# schematic.net
KiCad netlist of a schematic drawn in EasyEDA
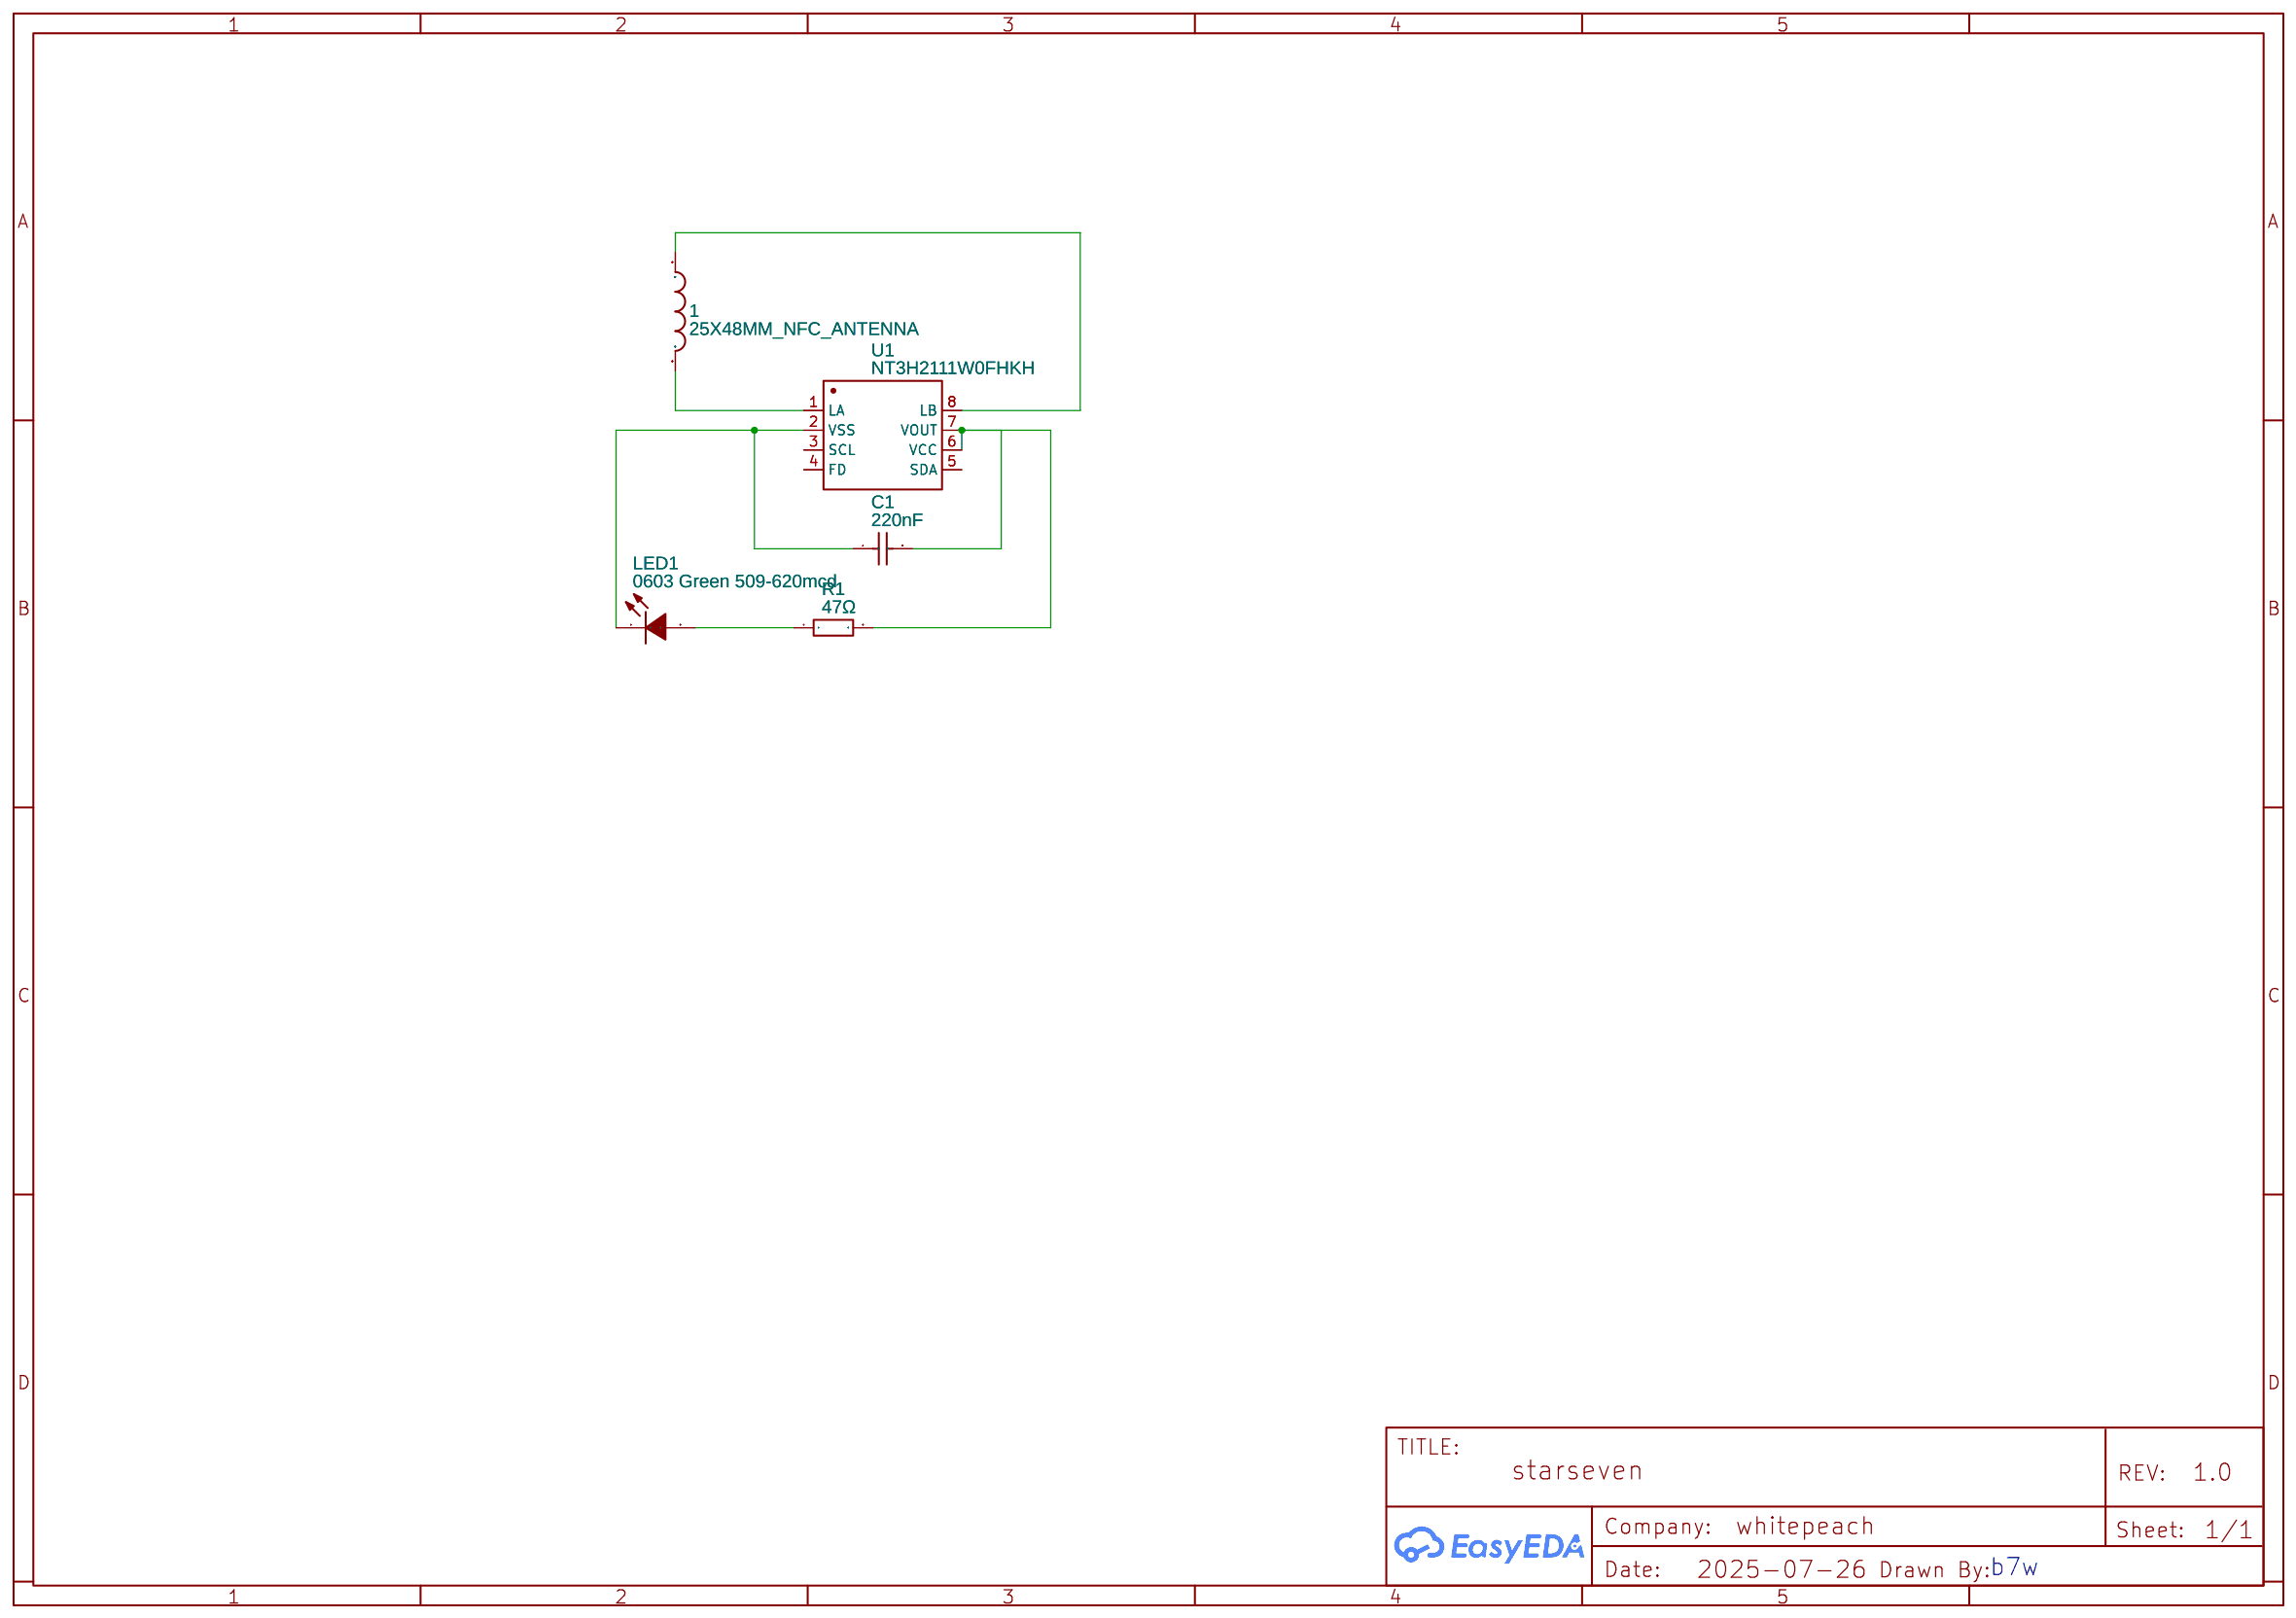
[diagram p0: schematic sheet]

(export (version "E")
  (design (tool "Eeschema 10.0.6"))
  (components
    (comp (ref "1") (value "25X48MM_NFC_ANTENNA") (libsource (lib "") (part "25X48MM_NFC_ANTENNA")))
    (comp (ref "C1")
      (value "220nF")
      (fields
        (field (name "Manufacturer Part") "CL10B224KA8NNNC")
        (field (name "Manufacturer") "SAMSUNG(三星)")
      )
      (libsource (lib "") (part "CL10B224KA8NNNC"))
    )
    (comp (ref "LED1")
      (value "0603 Green 509-620mcd")
      (fields (field (name "Manufacturer Part") "KT-0603G") (field (name "Manufacturer") "KENTO"))
      (libsource (lib "") (part "0603 Green 509-620mcd"))
    )
    (comp (ref "R1")
      (value "47Ω")
      (fields
        (field (name "Manufacturer Part") "0603WAF470JT5E")
        (field (name "Manufacturer") "UNI-ROYAL(厚声)")
      )
      (libsource (lib "") (part "0603WAF470JT5E"))
    )
    (comp (ref "U1")
      (value "NT3H2111W0FHKH")
      (fields (field (name "Manufacturer") "NXP(恩智浦)"))
      (libsource (lib "") (part "NT3H2111W0FHKH"))
    )
  )
  (nets
    (net (code "1") (name "Net-(LED1-A)") (class "Default")
      (node (ref "LED1") (pin "2") (pinfunction "A_2") (pintype "unspecified"))
      (node (ref "R1") (pin "1") (pinfunction "1_1") (pintype "input"))
    )
    (net (code "2") (name "Net-(LED1-K)") (class "Default")
      (node (ref "C1") (pin "1") (pinfunction "1_1") (pintype "input"))
      (node (ref "LED1") (pin "1") (pinfunction "K_1") (pintype "unspecified"))
      (node (ref "U1") (pin "2") (pinfunction "VSS_2") (pintype "unspecified"))
    )
    (net (code "3") (name "Net-(U1-LA)") (class "Default")
      (node (ref "1") (pin "P$2") (pinfunction "P$2_P$2") (pintype "bidirectional"))
      (node (ref "U1") (pin "1") (pinfunction "LA_1") (pintype "unspecified"))
    )
    (net (code "4") (name "Net-(U1-LB)") (class "Default")
      (node (ref "1") (pin "P$1") (pinfunction "P$1_P$1") (pintype "bidirectional"))
      (node (ref "U1") (pin "8") (pinfunction "LB_8") (pintype "unspecified"))
    )
    (net (code "5") (name "Net-(U1-VCC)") (class "Default")
      (node (ref "C1") (pin "2") (pinfunction "2_2") (pintype "input"))
      (node (ref "R1") (pin "2") (pinfunction "2_2") (pintype "input"))
      (node (ref "U1") (pin "6") (pinfunction "VCC_6") (pintype "unspecified"))
      (node (ref "U1") (pin "7") (pinfunction "VOUT_7") (pintype "unspecified"))
    )
    (net (code "6") (name "unconnected-(U1-FD-Pad4)") (class "Default")
      (node (ref "U1") (pin "4") (pinfunction "FD_4") (pintype "unspecified"))
    )
    (net (code "7") (name "unconnected-(U1-SCL-Pad3)") (class "Default")
      (node (ref "U1") (pin "3") (pinfunction "SCL_3") (pintype "unspecified"))
    )
    (net (code "8") (name "unconnected-(U1-SDA-Pad5)") (class "Default")
      (node (ref "U1") (pin "5") (pinfunction "SDA_5") (pintype "unspecified"))
    )
  )
)
